# medusa-ai-sensors.net
KiCad netlist of a schematic drawn in Altium Designer
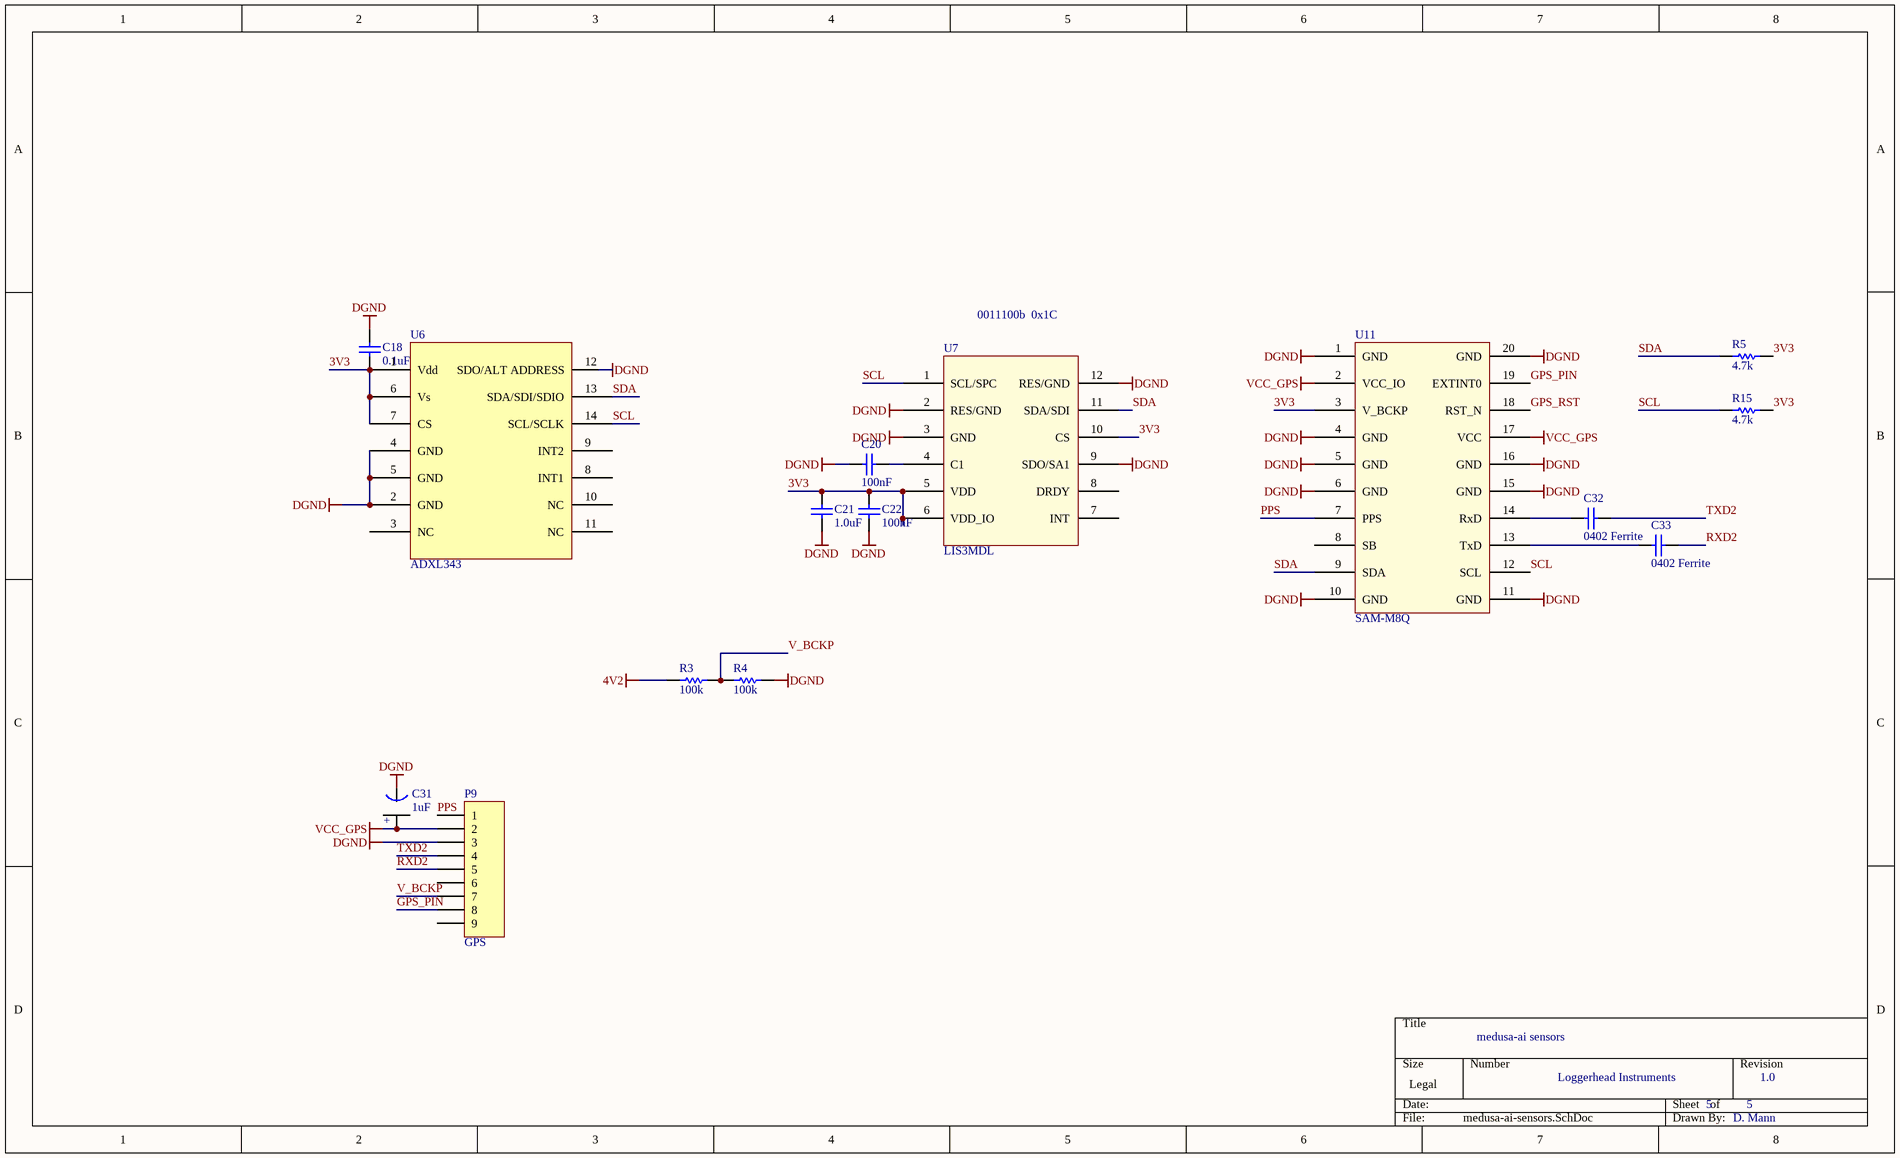
[diagram p0: medusa-ai-sensors.SchDoc]

(export (version "E")
  (design (tool "Eeschema 10.0.6"))
  (components
    (comp (ref "C18")
      (value "0.1uF")
      (footprint "0402")
      (description "Ceramic Chip Capacitor - Standard")
      (fields (field (name "PUBLISHER") "Altium Limited"))
      (libsource (lib "KEMET Chip Capacitor") (part "C0402"))
    )
    (comp (ref "C20")
      (value "100nF")
      (footprint "0402")
      (description "Ceramic Chip Capacitor - Standard")
      (fields (field (name "PUBLISHER") "Altium Limited"))
      (libsource (lib "KEMET Chip Capacitor") (part "C0402"))
    )
    (comp (ref "C21")
      (value "1.0uF")
      (footprint "0402")
      (description "Ceramic Chip Capacitor - Standard")
      (fields (field (name "PUBLISHER") "Altium Limited"))
      (libsource (lib "KEMET Chip Capacitor") (part "C0402"))
    )
    (comp (ref "C22")
      (value "100nF")
      (footprint "0402")
      (description "Ceramic Chip Capacitor - Standard")
      (fields (field (name "PUBLISHER") "Altium Limited"))
      (libsource (lib "KEMET Chip Capacitor") (part "C0402"))
    )
    (comp (ref "C31") (value "1uF") (footprint "Tant0805") (libsource (lib "Loggerhead") (part "Tant0805")))
    (comp (ref "C32")
      (value "0402 Ferrite")
      (footprint "0402")
      (description "Ceramic Chip Capacitor - Standard")
      (fields (field (name "PUBLISHER") "Altium Limited"))
      (libsource (lib "KEMET Chip Capacitor") (part "C0402"))
    )
    (comp (ref "C33")
      (value "0402 Ferrite")
      (footprint "0402")
      (description "Ceramic Chip Capacitor - Standard")
      (fields (field (name "PUBLISHER") "Altium Limited"))
      (libsource (lib "KEMET Chip Capacitor") (part "C0402"))
    )
    (comp (ref "P9")
      (value "GPS")
      (footprint "HDR1X9")
      (description "Header, 9-Pin")
      (fields (field (name "PUBLISHER") "Altium Limited"))
      (libsource (lib "Miscellaneous Connectors") (part "Header 9"))
    )
    (comp (ref "R3")
      (value "100k")
      (footprint "3-0603")
      (fields (field (name "PUBLISHER") "Altium Limited"))
      (libsource (lib "Panasonic Resistor") (part "ERJ3RK"))
    )
    (comp (ref "R4")
      (value "100k")
      (footprint "3-0603")
      (fields (field (name "PUBLISHER") "Altium Limited"))
      (libsource (lib "Panasonic Resistor") (part "ERJ3RK"))
    )
    (comp (ref "R5")
      (value "4.7k")
      (footprint "3-0603")
      (fields (field (name "PUBLISHER") "Altium Limited"))
      (libsource (lib "Panasonic Resistor") (part "ERJ3RK"))
    )
    (comp (ref "R15")
      (value "4.7k")
      (footprint "3-0603")
      (fields (field (name "PUBLISHER") "Altium Limited"))
      (libsource (lib "Panasonic Resistor") (part "ERJ3RK"))
    )
    (comp (ref "U6") (value "ADXL343") (footprint "ADXL345") (libsource (lib "Loggerhead") (part "ADXL345")))
    (comp (ref "U7")
      (value "LIS3MDL")
      (footprint "LGA-12")
      (description "magnetometer")
      (libsource (lib "Loggerhead") (part "LIS3MDL"))
    )
    (comp (ref "U11")
      (value "SAM-M8Q")
      (footprint "GPS SAM-MQ8")
      (libsource (lib "Loggerhead") (part "GPS SAM-M8Q"))
    )
  )
  (nets
    (net (code "1") (name "/3V3") (class "Default")
      (node (ref "C18") (pin "1") (pinfunction "1_1") (pintype "passive"))
      (node (ref "C21") (pin "1") (pinfunction "1_1") (pintype "passive"))
      (node (ref "C22") (pin "1") (pinfunction "1_1") (pintype "passive"))
      (node (ref "R15") (pin "2") (pinfunction "2_2") (pintype "passive"))
      (node (ref "R5") (pin "2") (pinfunction "2_2") (pintype "passive"))
      (node (ref "U11") (pin "3") (pinfunction "V_BCKP_3") (pintype "passive"))
      (node (ref "U6") (pin "1") (pinfunction "Vdd_1") (pintype "power_in"))
      (node (ref "U6") (pin "6") (pinfunction "Vs_6") (pintype "passive"))
      (node (ref "U6") (pin "7") (pinfunction "CS_7") (pintype "passive"))
      (node (ref "U7") (pin "10") (pinfunction "CS_10") (pintype "passive"))
      (node (ref "U7") (pin "5") (pinfunction "VDD_5") (pintype "passive"))
      (node (ref "U7") (pin "6") (pinfunction "VDD_IO_6") (pintype "passive"))
    )
    (net (code "2") (name "/GPS_PIN") (class "Default")
      (node (ref "P9") (pin "8") (pinfunction "8_8") (pintype "passive"))
      (node (ref "U11") (pin "19") (pinfunction "EXTINT0_19") (pintype "passive"))
    )
    (net (code "3") (name "/GPS_RST") (class "Default")
      (node (ref "U11") (pin "18") (pinfunction "RST_N_18") (pintype "passive"))
    )
    (net (code "4") (name "/PPS") (class "Default")
      (node (ref "P9") (pin "1") (pinfunction "1_1") (pintype "passive"))
      (node (ref "U11") (pin "7") (pinfunction "PPS_7") (pintype "passive"))
    )
    (net (code "5") (name "/RXD2") (class "Default")
      (node (ref "C33") (pin "2") (pinfunction "2_2") (pintype "passive"))
      (node (ref "P9") (pin "5") (pinfunction "5_5") (pintype "passive"))
    )
    (net (code "6") (name "/SCL") (class "Default")
      (node (ref "R15") (pin "1") (pinfunction "1_1") (pintype "passive"))
      (node (ref "U11") (pin "12") (pinfunction "SCL_12") (pintype "passive"))
      (node (ref "U6") (pin "14") (pinfunction "SCL/SCLK_14") (pintype "passive"))
      (node (ref "U7") (pin "1") (pinfunction "SCL/SPC_1") (pintype "passive"))
    )
    (net (code "7") (name "/SDA") (class "Default")
      (node (ref "R5") (pin "1") (pinfunction "1_1") (pintype "passive"))
      (node (ref "U11") (pin "9") (pinfunction "SDA_9") (pintype "passive"))
      (node (ref "U6") (pin "13") (pinfunction "SDA/SDI/SDIO_13") (pintype "passive"))
      (node (ref "U7") (pin "11") (pinfunction "SDA/SDI_11") (pintype "passive"))
    )
    (net (code "8") (name "/TXD2") (class "Default")
      (node (ref "C32") (pin "2") (pinfunction "2_2") (pintype "passive"))
      (node (ref "P9") (pin "4") (pinfunction "4_4") (pintype "passive"))
    )
    (net (code "9") (name "/V_BCKP") (class "Default")
      (node (ref "P9") (pin "7") (pinfunction "7_7") (pintype "passive"))
      (node (ref "R3") (pin "1") (pinfunction "1_1") (pintype "passive"))
      (node (ref "R4") (pin "2") (pinfunction "2_2") (pintype "passive"))
    )
    (net (code "10") (name "4V2") (class "Default")
      (node (ref "R3") (pin "2") (pinfunction "2_2") (pintype "passive"))
    )
    (net (code "11") (name "DGND") (class "Default")
      (node (ref "C18") (pin "2") (pinfunction "2_2") (pintype "passive"))
      (node (ref "C20") (pin "1") (pinfunction "1_1") (pintype "passive"))
      (node (ref "C21") (pin "2") (pinfunction "2_2") (pintype "passive"))
      (node (ref "C22") (pin "2") (pinfunction "2_2") (pintype "passive"))
      (node (ref "C31") (pin "1") (pinfunction "GND_1") (pintype "passive"))
      (node (ref "P9") (pin "3") (pinfunction "3_3") (pintype "passive"))
      (node (ref "R4") (pin "1") (pinfunction "1_1") (pintype "passive"))
      (node (ref "U11") (pin "1") (pinfunction "GND_1") (pintype "passive"))
      (node (ref "U11") (pin "10") (pinfunction "GND_10") (pintype "passive"))
      (node (ref "U11") (pin "11") (pinfunction "GND_11") (pintype "passive"))
      (node (ref "U11") (pin "15") (pinfunction "GND_15") (pintype "passive"))
      (node (ref "U11") (pin "16") (pinfunction "GND_16") (pintype "passive"))
      (node (ref "U11") (pin "20") (pinfunction "GND_20") (pintype "passive"))
      (node (ref "U11") (pin "4") (pinfunction "GND_4") (pintype "passive"))
      (node (ref "U11") (pin "5") (pinfunction "GND_5") (pintype "passive"))
      (node (ref "U11") (pin "6") (pinfunction "GND_6") (pintype "passive"))
      (node (ref "U6") (pin "12") (pinfunction "SDO/ALT_ADDRESS_12") (pintype "passive"))
      (node (ref "U6") (pin "2") (pinfunction "GND_2") (pintype "passive"))
      (node (ref "U6") (pin "4") (pinfunction "GND_4") (pintype "passive"))
      (node (ref "U6") (pin "5") (pinfunction "GND_5") (pintype "passive"))
      (node (ref "U7") (pin "12") (pinfunction "RES/GND_12") (pintype "passive"))
      (node (ref "U7") (pin "2") (pinfunction "RES/GND_2") (pintype "passive"))
      (node (ref "U7") (pin "3") (pinfunction "GND_3") (pintype "passive"))
      (node (ref "U7") (pin "9") (pinfunction "SDO/SA1_9") (pintype "passive"))
    )
    (net (code "12") (name "Net-(U7-C1)") (class "Default")
      (node (ref "C20") (pin "2") (pinfunction "2_2") (pintype "passive"))
      (node (ref "U7") (pin "4") (pinfunction "C1_4") (pintype "passive"))
    )
    (net (code "13") (name "Net-(U11-RxD)") (class "Default")
      (node (ref "C32") (pin "1") (pinfunction "1_1") (pintype "passive"))
      (node (ref "U11") (pin "14") (pinfunction "RxD_14") (pintype "passive"))
    )
    (net (code "14") (name "Net-(U11-TxD)") (class "Default")
      (node (ref "C33") (pin "1") (pinfunction "1_1") (pintype "passive"))
      (node (ref "U11") (pin "13") (pinfunction "TxD_13") (pintype "passive"))
    )
    (net (code "15") (name "VCC_GPS") (class "Default")
      (node (ref "C31") (pin "2") (pinfunction "+_2") (pintype "passive"))
      (node (ref "P9") (pin "2") (pinfunction "2_2") (pintype "passive"))
      (node (ref "U11") (pin "17") (pinfunction "VCC_17") (pintype "passive"))
      (node (ref "U11") (pin "2") (pinfunction "VCC_IO_2") (pintype "passive"))
    )
    (net (code "16") (name "unconnected-(P9-Pad6)") (class "Default")
      (node (ref "P9") (pin "6") (pinfunction "6_6") (pintype "passive"))
    )
    (net (code "17") (name "unconnected-(P9-Pad9)") (class "Default")
      (node (ref "P9") (pin "9") (pinfunction "9_9") (pintype "passive"))
    )
    (net (code "18") (name "unconnected-(U6-INT1-Pad8)") (class "Default")
      (node (ref "U6") (pin "8") (pinfunction "INT1_8") (pintype "passive"))
    )
    (net (code "19") (name "unconnected-(U6-INT2-Pad9)") (class "Default")
      (node (ref "U6") (pin "9") (pinfunction "INT2_9") (pintype "passive"))
    )
    (net (code "20") (name "unconnected-(U6-NC-Pad3)") (class "Default")
      (node (ref "U6") (pin "3") (pinfunction "NC_3") (pintype "passive"))
    )
    (net (code "21") (name "unconnected-(U6-NC-Pad10)") (class "Default")
      (node (ref "U6") (pin "10") (pinfunction "NC_10") (pintype "passive"))
    )
    (net (code "22") (name "unconnected-(U6-NC-Pad11)") (class "Default")
      (node (ref "U6") (pin "11") (pinfunction "NC_11") (pintype "passive"))
    )
    (net (code "23") (name "unconnected-(U7-DRDY-Pad8)") (class "Default")
      (node (ref "U7") (pin "8") (pinfunction "DRDY_8") (pintype "passive"))
    )
    (net (code "24") (name "unconnected-(U7-INT-Pad7)") (class "Default")
      (node (ref "U7") (pin "7") (pinfunction "INT_7") (pintype "passive"))
    )
    (net (code "25") (name "unconnected-(U11-SB-Pad8)") (class "Default")
      (node (ref "U11") (pin "8") (pinfunction "SB_8") (pintype "passive"))
    )
  )
)
